# dualHbridge-v3.net
KiCad netlist of a schematic drawn in EAGLE
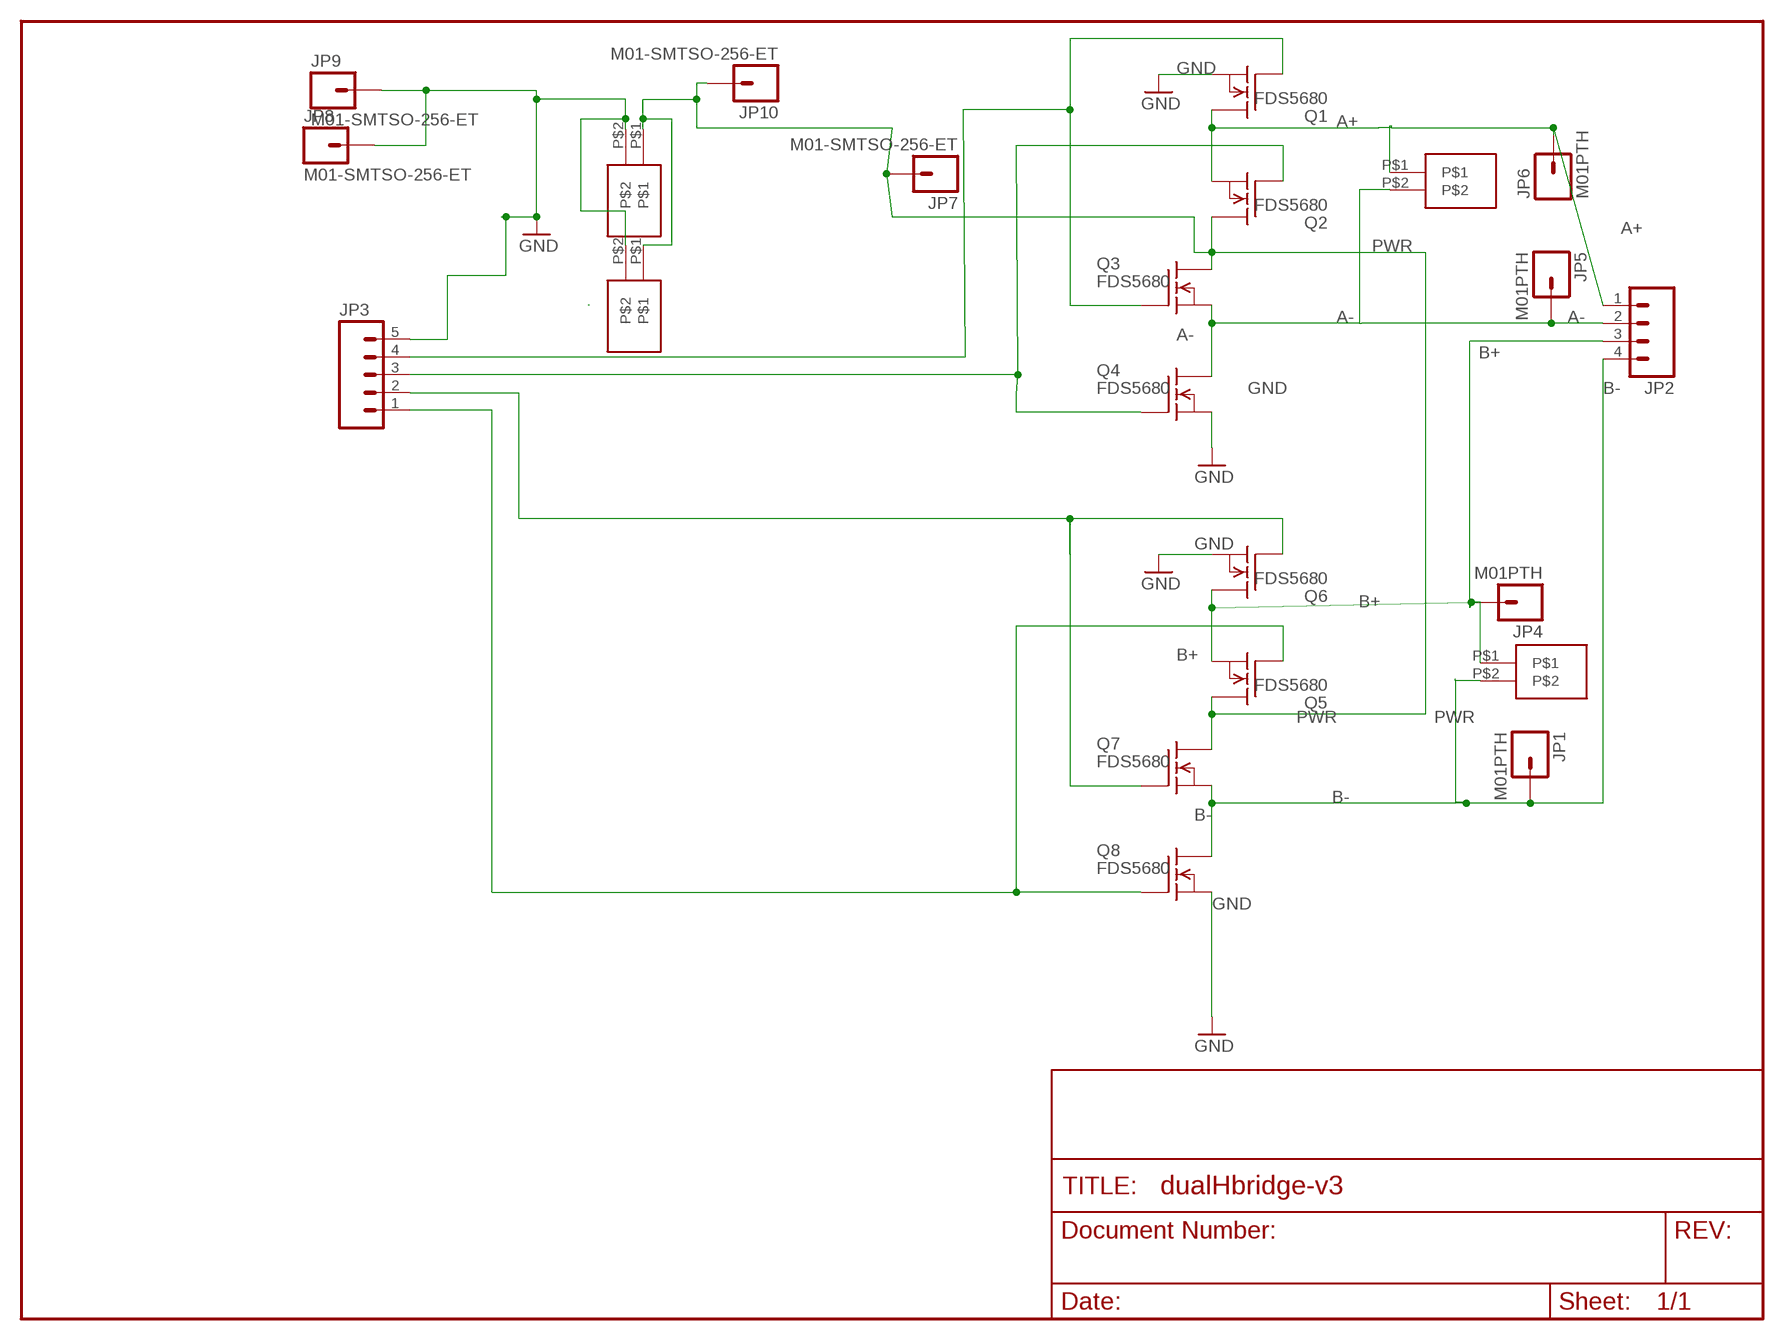
[diagram p0: schematic, sheet 1]

(export (version "E")
  (design (tool "Eeschema 10.0.6"))
  (components
    (comp (ref "JP1")
      (value "M01PTH")
      (footprint "eagle-import:1X01")
      (libsource (lib "eagle-import") (part "M01PTH"))
    )
    (comp (ref "JP2")
      (value "M04LONGPADS")
      (footprint "eagle-import:1X04_LONGPADS")
      (libsource (lib "eagle-import") (part "M04LONGPADS"))
    )
    (comp (ref "JP3")
      (value "M05PTH")
      (footprint "eagle-import:1X05")
      (libsource (lib "eagle-import") (part "M05PTH"))
    )
    (comp (ref "JP4")
      (value "M01PTH")
      (footprint "eagle-import:1X01")
      (libsource (lib "eagle-import") (part "M01PTH"))
    )
    (comp (ref "JP5")
      (value "M01PTH")
      (footprint "eagle-import:1X01")
      (libsource (lib "eagle-import") (part "M01PTH"))
    )
    (comp (ref "JP6")
      (value "M01PTH")
      (footprint "eagle-import:1X01")
      (libsource (lib "eagle-import") (part "M01PTH"))
    )
    (comp (ref "JP7")
      (value "M01-SMTSO-256-ET")
      (footprint "eagle-import:SMTSO-256-ET")
      (libsource (lib "eagle-import") (part "M01-SMTSO-256-ET"))
    )
    (comp (ref "JP8")
      (value "M01-SMTSO-256-ET")
      (footprint "eagle-import:SMTSO-256-ET")
      (libsource (lib "eagle-import") (part "M01-SMTSO-256-ET"))
    )
    (comp (ref "JP9")
      (value "M01-SMTSO-256-ET")
      (footprint "eagle-import:SMTSO-256-ET")
      (libsource (lib "eagle-import") (part "M01-SMTSO-256-ET"))
    )
    (comp (ref "JP10")
      (value "M01-SMTSO-256-ET")
      (footprint "eagle-import:SMTSO-256-ET")
      (libsource (lib "eagle-import") (part "M01-SMTSO-256-ET"))
    )
    (comp (ref "Q1")
      (value "FDS5680")
      (footprint "eagle-import:SO-8")
      (libsource (lib "eagle-import") (part "FDS5680"))
    )
    (comp (ref "Q2")
      (value "FDS5680")
      (footprint "eagle-import:SO-8")
      (libsource (lib "eagle-import") (part "FDS5680"))
    )
    (comp (ref "Q3")
      (value "FDS5680")
      (footprint "eagle-import:SO-8")
      (libsource (lib "eagle-import") (part "FDS5680"))
    )
    (comp (ref "Q4")
      (value "FDS5680")
      (footprint "eagle-import:SO-8")
      (libsource (lib "eagle-import") (part "FDS5680"))
    )
    (comp (ref "Q5")
      (value "FDS5680")
      (footprint "eagle-import:SO-8")
      (libsource (lib "eagle-import") (part "FDS5680"))
    )
    (comp (ref "Q6")
      (value "FDS5680")
      (footprint "eagle-import:SO-8")
      (libsource (lib "eagle-import") (part "FDS5680"))
    )
    (comp (ref "Q7")
      (value "FDS5680")
      (footprint "eagle-import:SO-8")
      (libsource (lib "eagle-import") (part "FDS5680"))
    )
    (comp (ref "Q8")
      (value "FDS5680")
      (footprint "eagle-import:SO-8")
      (libsource (lib "eagle-import") (part "FDS5680"))
    )
    (comp (ref "U$1")
      (value "SPRING-TERMINAL")
      (footprint "eagle-import:SPRING-TERMINAL")
      (libsource (lib "eagle-import") (part "SPRING-TERMINAL"))
    )
    (comp (ref "U$2")
      (value "SPRING-TERMINAL")
      (footprint "eagle-import:SPRING-TERMINAL")
      (libsource (lib "eagle-import") (part "SPRING-TERMINAL"))
    )
    (comp (ref "U$3")
      (value "SPRING-TERMINAL")
      (footprint "eagle-import:SPRING-TERMINAL")
      (libsource (lib "eagle-import") (part "SPRING-TERMINAL"))
    )
    (comp (ref "U$4")
      (value "SPRING-TERMINAL")
      (footprint "eagle-import:SPRING-TERMINAL")
      (libsource (lib "eagle-import") (part "SPRING-TERMINAL"))
    )
  )
  (nets
    (net (code "1") (name "/A+") (class "Default")
      (node (ref "JP2") (pin "1") (pinfunction "1_1") (pintype "passive"))
      (node (ref "JP6") (pin "1") (pinfunction "1_1") (pintype "passive"))
      (node (ref "Q1") (pin "5") (pinfunction "D_5") (pintype "passive"))
      (node (ref "Q1") (pin "6") (pinfunction "D_6") (pintype "passive"))
      (node (ref "Q1") (pin "7") (pinfunction "D_7") (pintype "passive"))
      (node (ref "Q1") (pin "8") (pinfunction "D_8") (pintype "passive"))
      (node (ref "Q2") (pin "1") (pinfunction "S_1") (pintype "passive"))
      (node (ref "Q2") (pin "2") (pinfunction "S_2") (pintype "passive"))
      (node (ref "Q2") (pin "3") (pinfunction "S_3") (pintype "passive"))
      (node (ref "U$1") (pin "P$1") (pinfunction "P$1_P$1") (pintype "bidirectional"))
    )
    (net (code "2") (name "/A-") (class "Default")
      (node (ref "JP2") (pin "2") (pinfunction "2_2") (pintype "passive"))
      (node (ref "JP5") (pin "1") (pinfunction "1_1") (pintype "passive"))
      (node (ref "Q3") (pin "1") (pinfunction "S_1") (pintype "passive"))
      (node (ref "Q3") (pin "2") (pinfunction "S_2") (pintype "passive"))
      (node (ref "Q3") (pin "3") (pinfunction "S_3") (pintype "passive"))
      (node (ref "Q4") (pin "5") (pinfunction "D_5") (pintype "passive"))
      (node (ref "Q4") (pin "6") (pinfunction "D_6") (pintype "passive"))
      (node (ref "Q4") (pin "7") (pinfunction "D_7") (pintype "passive"))
      (node (ref "Q4") (pin "8") (pinfunction "D_8") (pintype "passive"))
      (node (ref "U$1") (pin "P$2") (pinfunction "P$2_P$2") (pintype "bidirectional"))
    )
    (net (code "3") (name "/B+") (class "Default")
      (node (ref "JP2") (pin "3") (pinfunction "3_3") (pintype "passive"))
      (node (ref "JP4") (pin "1") (pinfunction "1_1") (pintype "passive"))
      (node (ref "Q5") (pin "1") (pinfunction "S_1") (pintype "passive"))
      (node (ref "Q5") (pin "2") (pinfunction "S_2") (pintype "passive"))
      (node (ref "Q5") (pin "3") (pinfunction "S_3") (pintype "passive"))
      (node (ref "Q6") (pin "5") (pinfunction "D_5") (pintype "passive"))
      (node (ref "Q6") (pin "6") (pinfunction "D_6") (pintype "passive"))
      (node (ref "Q6") (pin "7") (pinfunction "D_7") (pintype "passive"))
      (node (ref "Q6") (pin "8") (pinfunction "D_8") (pintype "passive"))
      (node (ref "U$3") (pin "P$1") (pinfunction "P$1_P$1") (pintype "bidirectional"))
    )
    (net (code "4") (name "/B-") (class "Default")
      (node (ref "JP1") (pin "1") (pinfunction "1_1") (pintype "passive"))
      (node (ref "JP2") (pin "4") (pinfunction "4_4") (pintype "passive"))
      (node (ref "Q7") (pin "1") (pinfunction "S_1") (pintype "passive"))
      (node (ref "Q7") (pin "2") (pinfunction "S_2") (pintype "passive"))
      (node (ref "Q7") (pin "3") (pinfunction "S_3") (pintype "passive"))
      (node (ref "Q8") (pin "5") (pinfunction "D_5") (pintype "passive"))
      (node (ref "Q8") (pin "6") (pinfunction "D_6") (pintype "passive"))
      (node (ref "Q8") (pin "7") (pinfunction "D_7") (pintype "passive"))
      (node (ref "Q8") (pin "8") (pinfunction "D_8") (pintype "passive"))
      (node (ref "U$3") (pin "P$2") (pinfunction "P$2_P$2") (pintype "bidirectional"))
    )
    (net (code "5") (name "/PWR") (class "Default")
      (node (ref "JP10") (pin "P$1") (pinfunction "1_P$1") (pintype "passive"))
      (node (ref "JP7") (pin "P$1") (pinfunction "1_P$1") (pintype "passive"))
      (node (ref "Q2") (pin "5") (pinfunction "D_5") (pintype "passive"))
      (node (ref "Q2") (pin "6") (pinfunction "D_6") (pintype "passive"))
      (node (ref "Q2") (pin "7") (pinfunction "D_7") (pintype "passive"))
      (node (ref "Q2") (pin "8") (pinfunction "D_8") (pintype "passive"))
      (node (ref "Q3") (pin "5") (pinfunction "D_5") (pintype "passive"))
      (node (ref "Q3") (pin "6") (pinfunction "D_6") (pintype "passive"))
      (node (ref "Q3") (pin "7") (pinfunction "D_7") (pintype "passive"))
      (node (ref "Q3") (pin "8") (pinfunction "D_8") (pintype "passive"))
      (node (ref "Q5") (pin "5") (pinfunction "D_5") (pintype "passive"))
      (node (ref "Q5") (pin "6") (pinfunction "D_6") (pintype "passive"))
      (node (ref "Q5") (pin "7") (pinfunction "D_7") (pintype "passive"))
      (node (ref "Q5") (pin "8") (pinfunction "D_8") (pintype "passive"))
      (node (ref "Q7") (pin "5") (pinfunction "D_5") (pintype "passive"))
      (node (ref "Q7") (pin "6") (pinfunction "D_6") (pintype "passive"))
      (node (ref "Q7") (pin "7") (pinfunction "D_7") (pintype "passive"))
      (node (ref "Q7") (pin "8") (pinfunction "D_8") (pintype "passive"))
      (node (ref "U$2") (pin "P$1") (pinfunction "P$1_P$1") (pintype "bidirectional"))
      (node (ref "U$4") (pin "P$1") (pinfunction "P$1_P$1") (pintype "bidirectional"))
    )
    (net (code "6") (name "GND") (class "Default")
      (node (ref "JP3") (pin "5") (pinfunction "5_5") (pintype "passive"))
      (node (ref "JP8") (pin "P$1") (pinfunction "1_P$1") (pintype "passive"))
      (node (ref "JP9") (pin "P$1") (pinfunction "1_P$1") (pintype "passive"))
      (node (ref "Q1") (pin "1") (pinfunction "S_1") (pintype "passive"))
      (node (ref "Q1") (pin "2") (pinfunction "S_2") (pintype "passive"))
      (node (ref "Q1") (pin "3") (pinfunction "S_3") (pintype "passive"))
      (node (ref "Q4") (pin "1") (pinfunction "S_1") (pintype "passive"))
      (node (ref "Q4") (pin "2") (pinfunction "S_2") (pintype "passive"))
      (node (ref "Q4") (pin "3") (pinfunction "S_3") (pintype "passive"))
      (node (ref "Q6") (pin "1") (pinfunction "S_1") (pintype "passive"))
      (node (ref "Q6") (pin "2") (pinfunction "S_2") (pintype "passive"))
      (node (ref "Q6") (pin "3") (pinfunction "S_3") (pintype "passive"))
      (node (ref "Q8") (pin "1") (pinfunction "S_1") (pintype "passive"))
      (node (ref "Q8") (pin "2") (pinfunction "S_2") (pintype "passive"))
      (node (ref "Q8") (pin "3") (pinfunction "S_3") (pintype "passive"))
      (node (ref "U$2") (pin "P$2") (pinfunction "P$2_P$2") (pintype "bidirectional"))
      (node (ref "U$4") (pin "P$2") (pinfunction "P$2_P$2") (pintype "bidirectional"))
    )
    (net (code "7") (name "Net-(Q1-G)") (class "Default")
      (node (ref "JP3") (pin "4") (pinfunction "4_4") (pintype "passive"))
      (node (ref "Q1") (pin "4") (pinfunction "G_4") (pintype "passive"))
      (node (ref "Q3") (pin "4") (pinfunction "G_4") (pintype "passive"))
    )
    (net (code "8") (name "Net-(Q2-G)") (class "Default")
      (node (ref "JP3") (pin "3") (pinfunction "3_3") (pintype "passive"))
      (node (ref "Q2") (pin "4") (pinfunction "G_4") (pintype "passive"))
      (node (ref "Q4") (pin "4") (pinfunction "G_4") (pintype "passive"))
    )
    (net (code "9") (name "Net-(Q5-G)") (class "Default")
      (node (ref "JP3") (pin "1") (pinfunction "1_1") (pintype "passive"))
      (node (ref "Q5") (pin "4") (pinfunction "G_4") (pintype "passive"))
      (node (ref "Q8") (pin "4") (pinfunction "G_4") (pintype "passive"))
    )
    (net (code "10") (name "Net-(Q6-G)") (class "Default")
      (node (ref "JP3") (pin "2") (pinfunction "2_2") (pintype "passive"))
      (node (ref "Q6") (pin "4") (pinfunction "G_4") (pintype "passive"))
      (node (ref "Q7") (pin "4") (pinfunction "G_4") (pintype "passive"))
    )
  )
)
